# droneM.net
KiCad netlist of a schematic drawn in Altium Designer
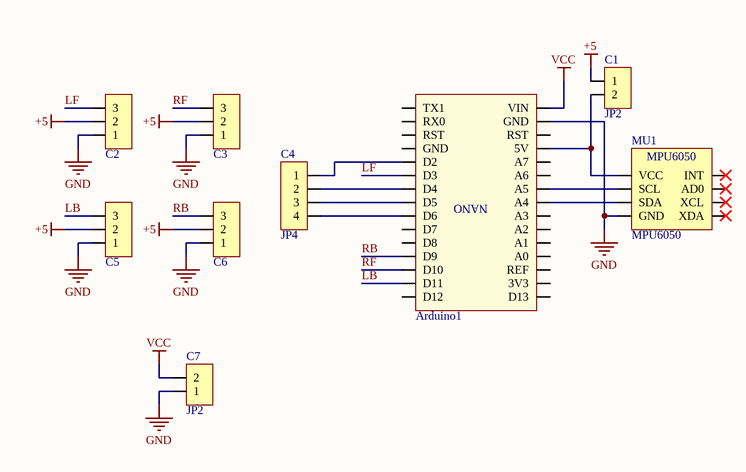
[diagram p0: droneM.SchDoc]

(export (version "E")
  (design (tool "Eeschema 10.0.6"))
  (components
    (comp (ref "Arduino1")
      (value "Arduino Nano")
      (footprint "Arduino Nano")
      (description "Arduino NANO")
      (libsource (lib "LIBRARY") (part "Arduino Nano"))
    )
    (comp (ref "C1")
      (value "JP2")
      (footprint "JP2-CLOSED")
      (description "WR-PHD 2.54 mm Angled Socket Header")
      (fields
        (field (name "MANUFACTURER") "Würth Elektronik eiSos GmbH")
        (field (name "PARTNO") "613002143121")
        (field (name "CREATED BY") "Karrer Zheng")
      )
      (libsource (lib "LIBRARY") (part "JP2"))
    )
    (comp (ref "C2")
      (value "JP3")
      (footprint "JP3-C1T")
      (description "WR-PHD 2.54 mm Angled Socket Header")
      (fields
        (field (name "MANUFACTURER") "Würth Elektronik eiSos GmbH")
        (field (name "PARTNO") "613003143121")
        (field (name "CREATED BY") "Karrer Zheng")
      )
      (libsource (lib "LIBRARY") (part "JP3"))
    )
    (comp (ref "C3")
      (value "JP3")
      (footprint "JP3-C1T")
      (description "WR-PHD 2.54 mm Angled Socket Header")
      (fields
        (field (name "MANUFACTURER") "Würth Elektronik eiSos GmbH")
        (field (name "PARTNO") "613003143121")
        (field (name "CREATED BY") "Karrer Zheng")
      )
      (libsource (lib "LIBRARY") (part "JP3"))
    )
    (comp (ref "C4")
      (value "JP4")
      (footprint "JP4-C1T")
      (description "WR-PHD 2.54 mm Angled Socket Header")
      (fields
        (field (name "MANUFACTURER") "Würth Elektronik eiSos GmbH")
        (field (name "PARTNO") "613004143121")
        (field (name "CREATED BY") "Karrer Zheng")
      )
      (libsource (lib "LIBRARY") (part "JP4"))
    )
    (comp (ref "C5")
      (value "JP3")
      (footprint "JP3-C1T")
      (description "WR-PHD 2.54 mm Angled Socket Header")
      (fields
        (field (name "MANUFACTURER") "Würth Elektronik eiSos GmbH")
        (field (name "PARTNO") "613003143121")
        (field (name "CREATED BY") "Karrer Zheng")
      )
      (libsource (lib "LIBRARY") (part "JP3"))
    )
    (comp (ref "C6")
      (value "JP3")
      (footprint "JP3-C1T")
      (description "WR-PHD 2.54 mm Angled Socket Header")
      (fields
        (field (name "MANUFACTURER") "Würth Elektronik eiSos GmbH")
        (field (name "PARTNO") "613003143121")
        (field (name "CREATED BY") "Karrer Zheng")
      )
      (libsource (lib "LIBRARY") (part "JP3"))
    )
    (comp (ref "C7")
      (value "JP2")
      (footprint "JP2-C1T")
      (description "WR-PHD 2.54 mm Angled Socket Header")
      (fields
        (field (name "MANUFACTURER") "Würth Elektronik eiSos GmbH")
        (field (name "PARTNO") "613002143121")
        (field (name "CREATED BY") "Karrer Zheng")
      )
      (libsource (lib "") (part "JP2_1"))
    )
    (comp (ref "MU1")
      (value "MPU6050")
      (footprint "MPU6050")
      (fields
        (field (name "MANUFACTURER") "Würth Elektronik eiSos GmbH")
        (field (name "PARTNO") "613004143121")
        (field (name "CREATED BY") "Karrer Zheng")
      )
      (libsource (lib "LIBRARY") (part "MPU6050"))
    )
  )
  (nets
    (net (code "1") (name "+5") (class "Default")
      (node (ref "C1") (pin "1") (pinfunction "1_1") (pintype "passive"))
      (node (ref "C2") (pin "2") (pinfunction "2_2") (pintype "passive"))
      (node (ref "C3") (pin "2") (pinfunction "2_2") (pintype "passive"))
      (node (ref "C5") (pin "2") (pinfunction "2_2") (pintype "passive"))
      (node (ref "C6") (pin "2") (pinfunction "2_2") (pintype "passive"))
    )
    (net (code "2") (name "/LB") (class "Default")
      (node (ref "Arduino1") (pin "D11") (pinfunction "D11_D11") (pintype "passive"))
      (node (ref "C5") (pin "3") (pinfunction "3_3") (pintype "passive"))
    )
    (net (code "3") (name "/LF") (class "Default")
      (node (ref "Arduino1") (pin "D3") (pinfunction "D3_D3") (pintype "passive"))
      (node (ref "C2") (pin "3") (pinfunction "3_3") (pintype "passive"))
    )
    (net (code "4") (name "/RB") (class "Default")
      (node (ref "Arduino1") (pin "D9") (pinfunction "D9_D9") (pintype "passive"))
      (node (ref "C6") (pin "3") (pinfunction "3_3") (pintype "passive"))
    )
    (net (code "5") (name "/RF") (class "Default")
      (node (ref "Arduino1") (pin "D10") (pinfunction "D10_D10") (pintype "passive"))
      (node (ref "C3") (pin "3") (pinfunction "3_3") (pintype "passive"))
    )
    (net (code "6") (name "GND") (class "Default")
      (node (ref "Arduino1") (pin "GND") (pinfunction "GND_GND") (pintype "passive"))
      (node (ref "C2") (pin "1") (pinfunction "1_1") (pintype "passive"))
      (node (ref "C3") (pin "1") (pinfunction "1_1") (pintype "passive"))
      (node (ref "C5") (pin "1") (pinfunction "1_1") (pintype "passive"))
      (node (ref "C6") (pin "1") (pinfunction "1_1") (pintype "passive"))
      (node (ref "C7") (pin "1") (pinfunction "1_1") (pintype "passive"))
      (node (ref "MU1") (pin "2") (pinfunction "GND_2") (pintype "passive"))
    )
    (net (code "7") (name "Net-(Arduino1-PadD2)") (class "Default")
      (node (ref "Arduino1") (pin "D2") (pinfunction "D2_D2") (pintype "passive"))
      (node (ref "C4") (pin "1") (pinfunction "1_1") (pintype "passive"))
    )
    (net (code "8") (name "Net-(Arduino1-PadD4)") (class "Default")
      (node (ref "Arduino1") (pin "D4") (pinfunction "D4_D4") (pintype "passive"))
      (node (ref "C4") (pin "2") (pinfunction "2_2") (pintype "passive"))
    )
    (net (code "9") (name "Net-(Arduino1-PadD5)") (class "Default")
      (node (ref "Arduino1") (pin "D5") (pinfunction "D5_D5") (pintype "passive"))
      (node (ref "C4") (pin "3") (pinfunction "3_3") (pintype "passive"))
    )
    (net (code "10") (name "Net-(Arduino1-PadD6)") (class "Default")
      (node (ref "Arduino1") (pin "D6") (pinfunction "D6_D6") (pintype "passive"))
      (node (ref "C4") (pin "4") (pinfunction "4_4") (pintype "passive"))
    )
    (net (code "11") (name "Net-(MU1-SCL)") (class "Default")
      (node (ref "Arduino1") (pin "A5") (pinfunction "A5_A5") (pintype "passive"))
      (node (ref "MU1") (pin "3") (pinfunction "SCL_3") (pintype "passive"))
    )
    (net (code "12") (name "Net-(MU1-SDA)") (class "Default")
      (node (ref "Arduino1") (pin "A4") (pinfunction "A4_A4") (pintype "passive"))
      (node (ref "MU1") (pin "4") (pinfunction "SDA_4") (pintype "passive"))
    )
    (net (code "13") (name "Net-(MU1-VCC)") (class "Default")
      (node (ref "Arduino1") (pin "5V") (pinfunction "5V_5V") (pintype "passive"))
      (node (ref "C1") (pin "2") (pinfunction "2_2") (pintype "passive"))
      (node (ref "MU1") (pin "1") (pinfunction "VCC_1") (pintype "passive"))
    )
    (net (code "14") (name "VCC") (class "Default")
      (node (ref "Arduino1") (pin "VIN") (pinfunction "VIN_VIN") (pintype "passive"))
      (node (ref "C7") (pin "2") (pinfunction "2_2") (pintype "passive"))
    )
    (net (code "15") (name "unconnected-(Arduino1-Pad3V3)") (class "Default")
      (node (ref "Arduino1") (pin "3V3") (pinfunction "3V3_3V3") (pintype "passive"))
    )
    (net (code "16") (name "unconnected-(Arduino1-PadA0)") (class "Default")
      (node (ref "Arduino1") (pin "A0") (pinfunction "A0_A0") (pintype "passive"))
    )
    (net (code "17") (name "unconnected-(Arduino1-PadA1)") (class "Default")
      (node (ref "Arduino1") (pin "A1") (pinfunction "A1_A1") (pintype "passive"))
    )
    (net (code "18") (name "unconnected-(Arduino1-PadA2)") (class "Default")
      (node (ref "Arduino1") (pin "A2") (pinfunction "A2_A2") (pintype "passive"))
    )
    (net (code "19") (name "unconnected-(Arduino1-PadA3)") (class "Default")
      (node (ref "Arduino1") (pin "A3") (pinfunction "A3_A3") (pintype "passive"))
    )
    (net (code "20") (name "unconnected-(Arduino1-PadA6)") (class "Default")
      (node (ref "Arduino1") (pin "A6") (pinfunction "A6_A6") (pintype "passive"))
    )
    (net (code "21") (name "unconnected-(Arduino1-PadA7)") (class "Default")
      (node (ref "Arduino1") (pin "A7") (pinfunction "A7_A7") (pintype "passive"))
    )
    (net (code "22") (name "unconnected-(Arduino1-PadD7)") (class "Default")
      (node (ref "Arduino1") (pin "D7") (pinfunction "D7_D7") (pintype "passive"))
    )
    (net (code "23") (name "unconnected-(Arduino1-PadD8)") (class "Default")
      (node (ref "Arduino1") (pin "D8") (pinfunction "D8_D8") (pintype "passive"))
    )
    (net (code "24") (name "unconnected-(Arduino1-PadD12)") (class "Default")
      (node (ref "Arduino1") (pin "D12") (pinfunction "D12_D12") (pintype "passive"))
    )
    (net (code "25") (name "unconnected-(Arduino1-PadD13)") (class "Default")
      (node (ref "Arduino1") (pin "D13") (pinfunction "D13_D13") (pintype "passive"))
    )
    (net (code "26") (name "unconnected-(Arduino1-PadGND)") (class "Default")
      (node (ref "Arduino1") (pin "GND") (pinfunction "GND_GND") (pintype "passive"))
    )
    (net (code "27") (name "unconnected-(Arduino1-PadREF)") (class "Default")
      (node (ref "Arduino1") (pin "REF") (pinfunction "REF_REF") (pintype "passive"))
    )
    (net (code "28") (name "unconnected-(Arduino1-PadRST)") (class "Default")
      (node (ref "Arduino1") (pin "RST") (pinfunction "RST_RST") (pintype "passive"))
    )
    (net (code "29") (name "unconnected-(Arduino1-PadRST)_1") (class "Default")
      (node (ref "Arduino1") (pin "RST") (pinfunction "RST_RST") (pintype "passive"))
    )
    (net (code "30") (name "unconnected-(Arduino1-PadRX0)") (class "Default")
      (node (ref "Arduino1") (pin "RX0") (pinfunction "RX0_RX0") (pintype "passive"))
    )
    (net (code "31") (name "unconnected-(Arduino1-PadTX1)") (class "Default")
      (node (ref "Arduino1") (pin "TX1") (pinfunction "TX1_TX1") (pintype "passive"))
    )
    (net (code "32") (name "unconnected-(MU1-AD0-Pad7)") (class "Default")
      (node (ref "MU1") (pin "7") (pinfunction "AD0_7") (pintype "passive+no_connect"))
    )
    (net (code "33") (name "unconnected-(MU1-INT-Pad8)") (class "Default")
      (node (ref "MU1") (pin "8") (pinfunction "INT_8") (pintype "passive+no_connect"))
    )
    (net (code "34") (name "unconnected-(MU1-XCL-Pad6)") (class "Default")
      (node (ref "MU1") (pin "6") (pinfunction "XCL_6") (pintype "passive+no_connect"))
    )
    (net (code "35") (name "unconnected-(MU1-XDA-Pad5)") (class "Default")
      (node (ref "MU1") (pin "5") (pinfunction "XDA_5") (pintype "passive+no_connect"))
    )
  )
)
